# Platine_2_smd.net
KiCad netlist of a schematic drawn in EAGLE
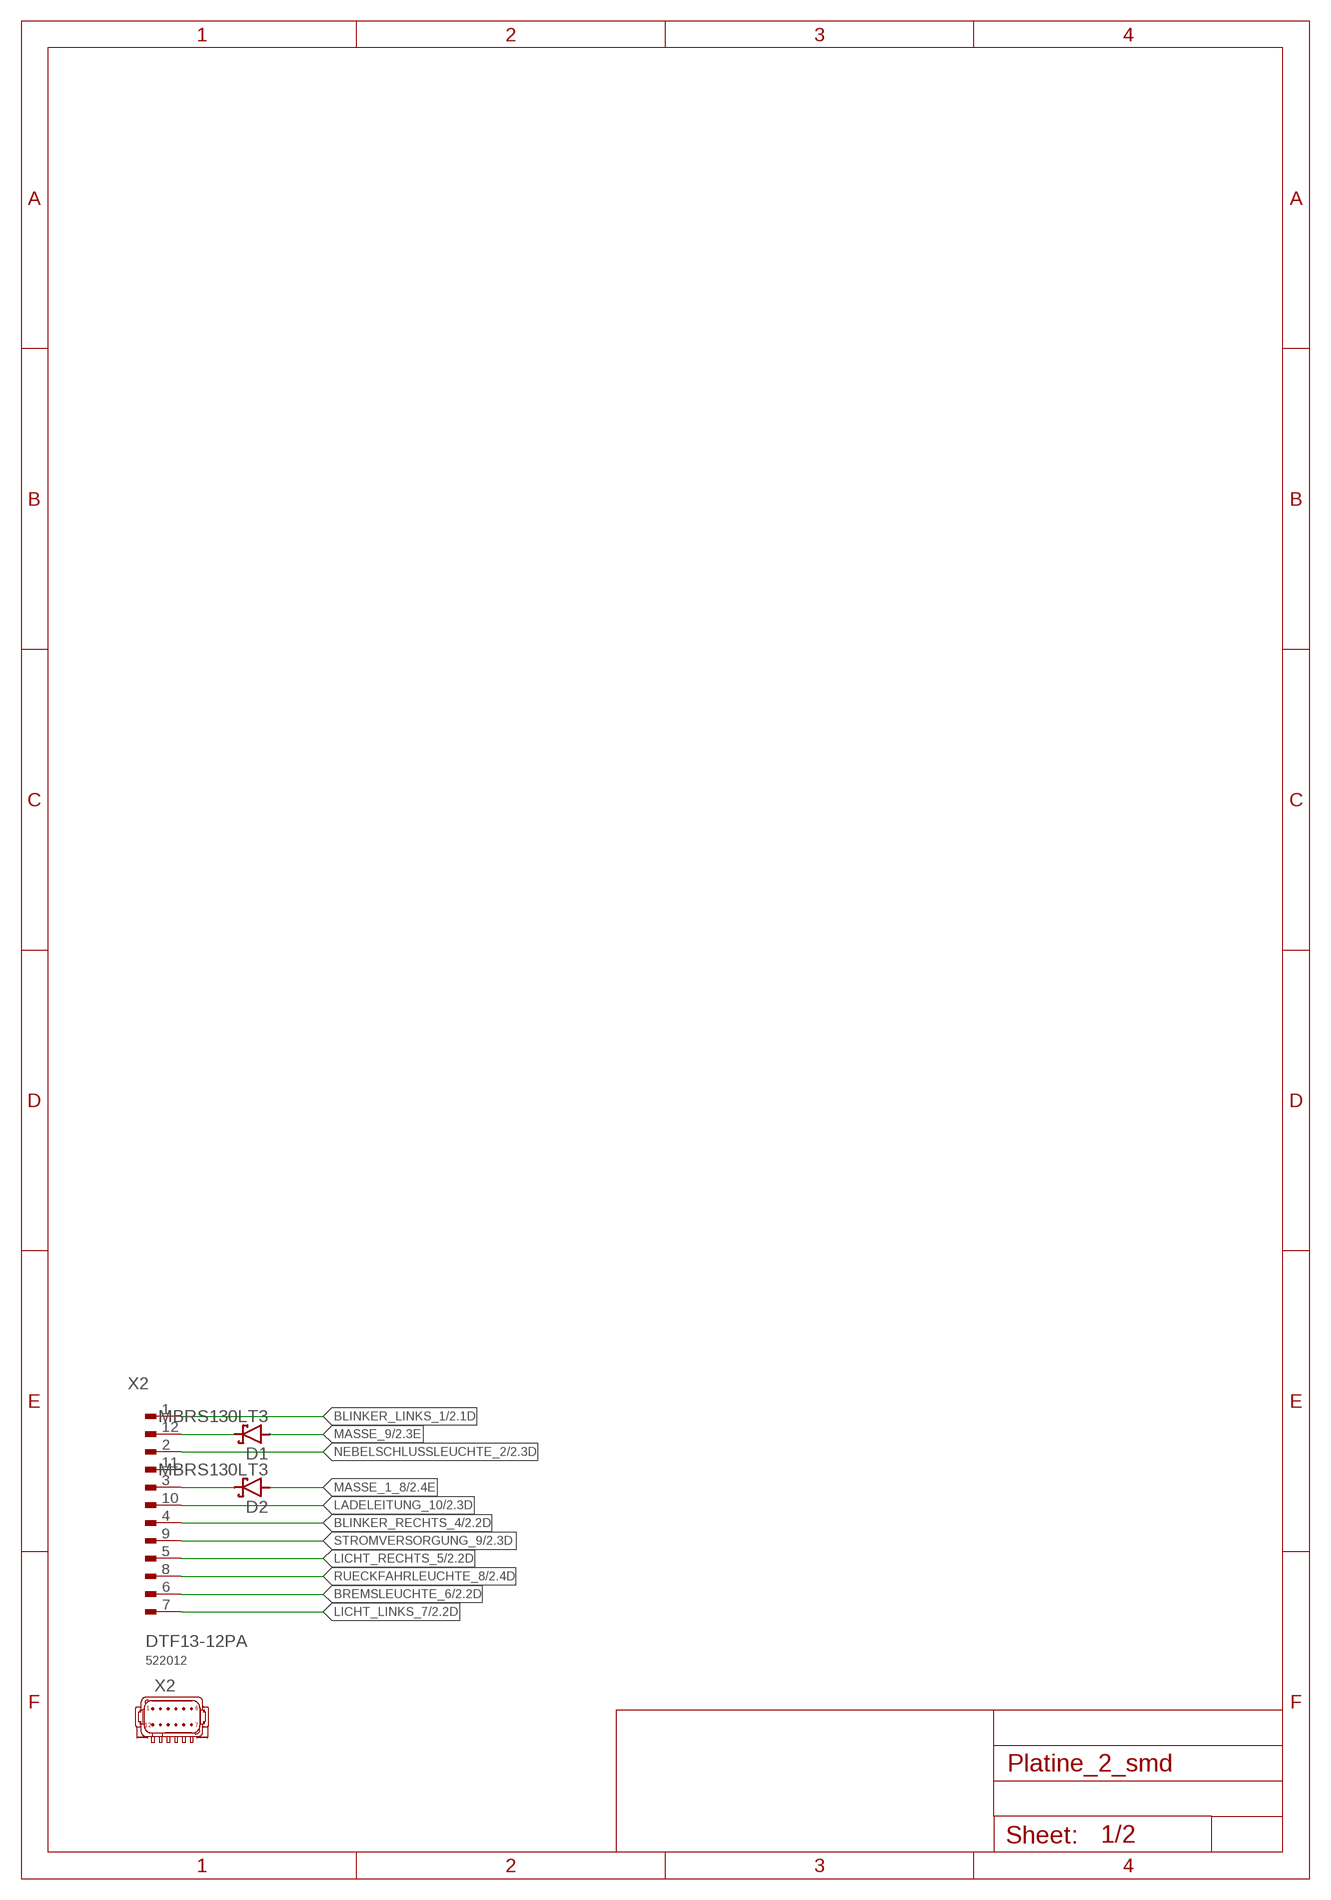
[diagram p0: schematic, sheet 1]
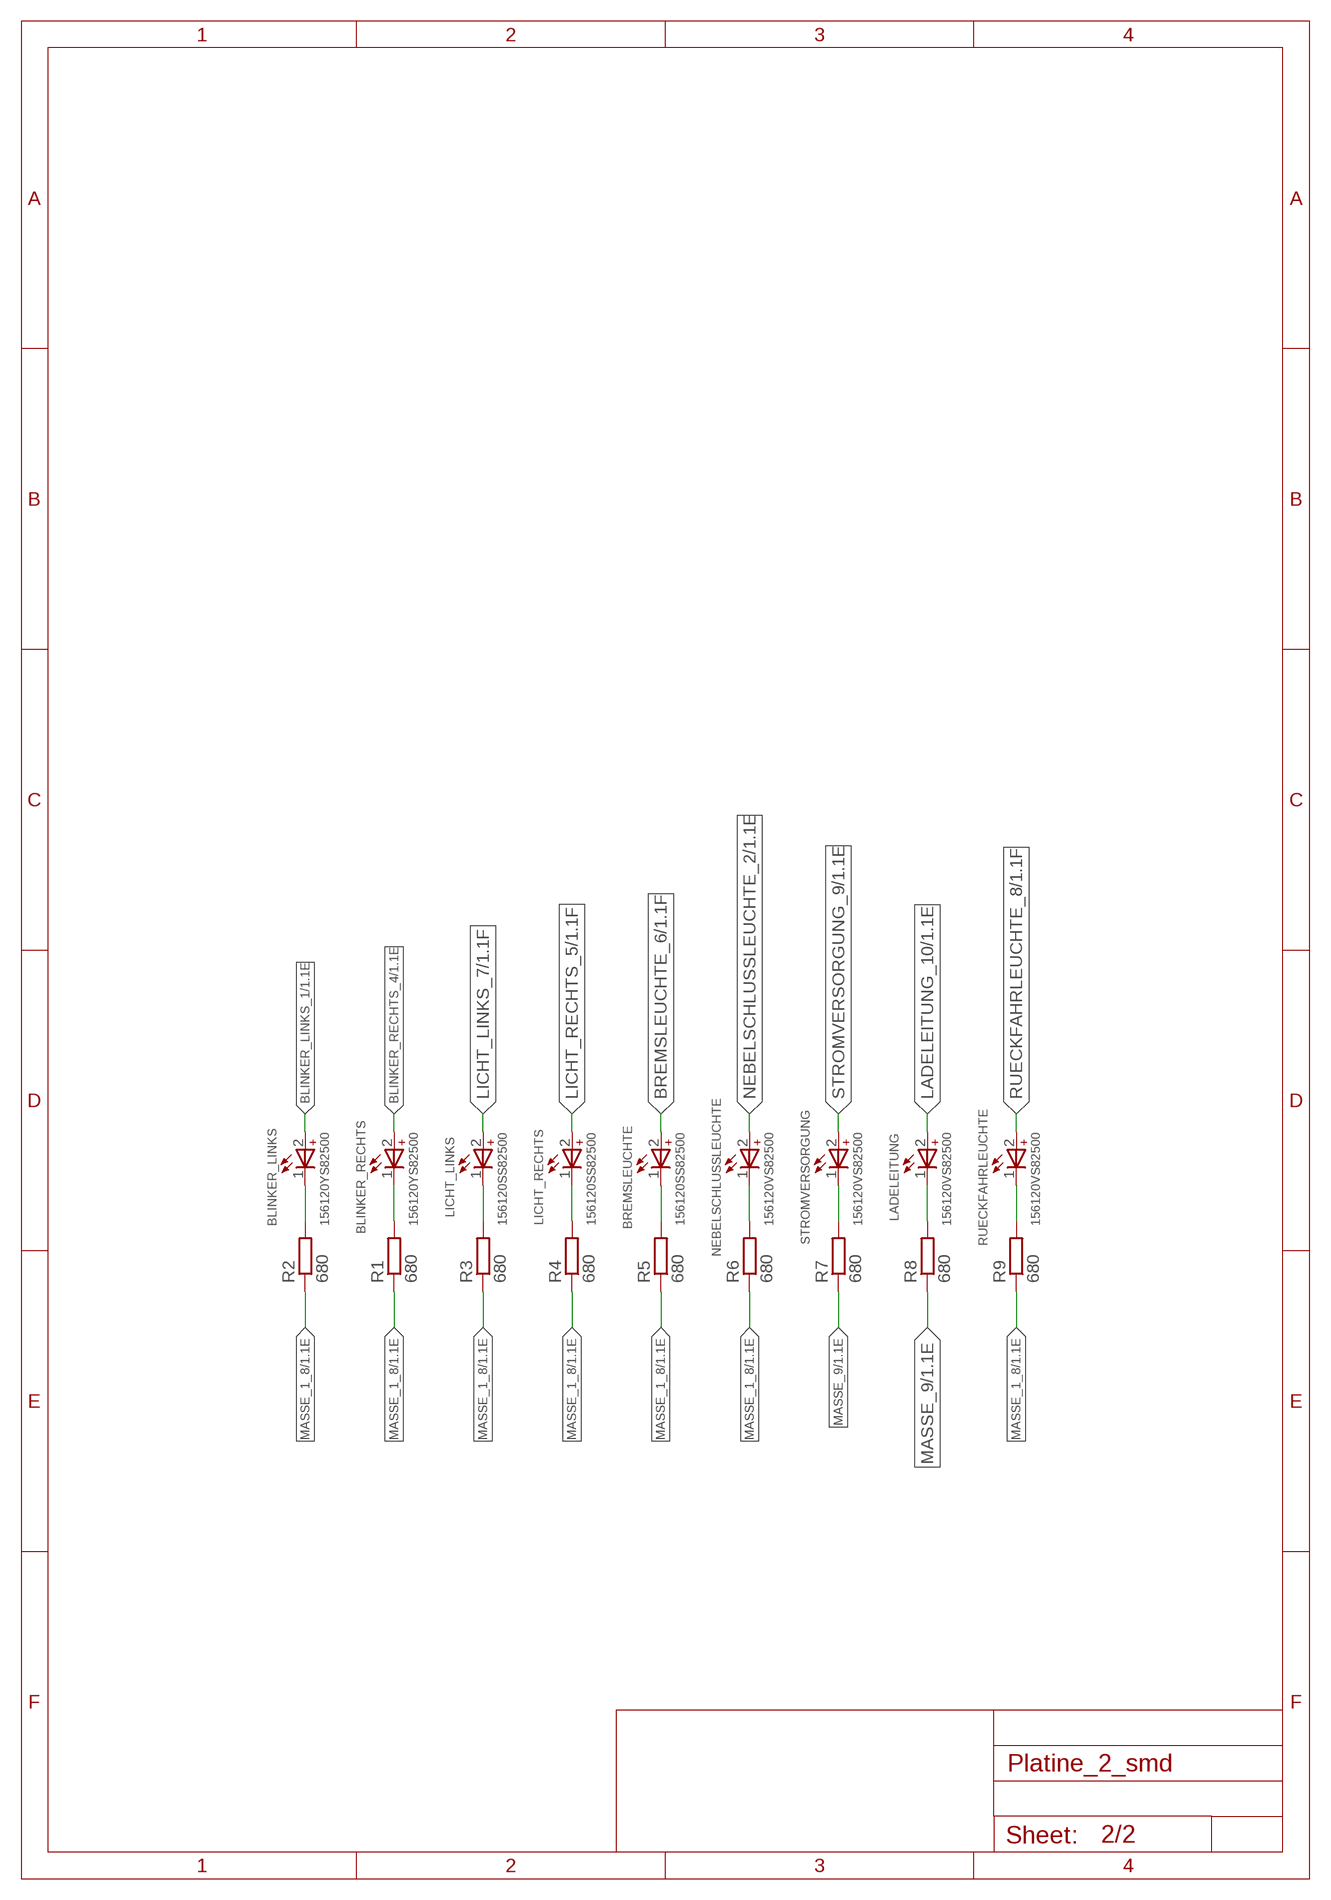
[diagram p1: schematic, sheet 2]

(export (version "E")
  (design (tool "Eeschema 10.0.6"))
  (components
    (comp (ref "BLINKER_LINKS")
      (value "156120YS82500")
      (footprint "eagle-import:WL-SMRW_1206_DOME_REV")
      (libsource (lib "eagle-import") (part "WL-SMRW_1206_DOME_REV_156120YS82500"))
    )
    (comp (ref "BLINKER_RECHTS")
      (value "156120YS82500")
      (footprint "eagle-import:WL-SMRW_1206_DOME_REV")
      (libsource (lib "eagle-import") (part "WL-SMRW_1206_DOME_REV_156120YS82500"))
    )
    (comp (ref "BREMSLEUCHTE")
      (value "156120SS82500")
      (footprint "eagle-import:WL-SMRW_1206_DOME_REV")
      (libsource (lib "eagle-import") (part "WL-SMRW_1206_DOME_REV_156120SS82500"))
    )
    (comp (ref "LADELEITUNG")
      (value "156120VS82500")
      (footprint "eagle-import:WL-SMRW_1206_DOME_REV")
      (libsource (lib "eagle-import") (part "WL-SMRW_1206_DOME_REV_156120SS82500"))
    )
    (comp (ref "LICHT_LINKS")
      (value "156120SS82500")
      (footprint "eagle-import:WL-SMRW_1206_DOME_REV")
      (libsource (lib "eagle-import") (part "WL-SMRW_1206_DOME_REV_156120SS82500"))
    )
    (comp (ref "LICHT_RECHTS")
      (value "156120SS82500")
      (footprint "eagle-import:WL-SMRW_1206_DOME_REV")
      (libsource (lib "eagle-import") (part "WL-SMRW_1206_DOME_REV_156120SS82500"))
    )
    (comp (ref "NEBELSCHLUSSLEUCHTE")
      (value "156120VS82500")
      (footprint "eagle-import:WL-SMRW_1206_DOME_REV")
      (libsource (lib "eagle-import") (part "WL-SMRW_1206_DOME_REV_156120SS82500"))
    )
    (comp (ref "R1")
      (value "680")
      (footprint "eagle-import:R1206")
      (libsource (lib "eagle-import") (part "R-EU_R1206"))
    )
    (comp (ref "R2")
      (value "680")
      (footprint "eagle-import:R1206")
      (libsource (lib "eagle-import") (part "R-EU_R1206"))
    )
    (comp (ref "R3")
      (value "680")
      (footprint "eagle-import:R1206")
      (libsource (lib "eagle-import") (part "R-EU_R1206"))
    )
    (comp (ref "R4")
      (value "680")
      (footprint "eagle-import:R1206")
      (libsource (lib "eagle-import") (part "R-EU_R1206"))
    )
    (comp (ref "R5")
      (value "680")
      (footprint "eagle-import:R1206")
      (libsource (lib "eagle-import") (part "R-EU_R1206"))
    )
    (comp (ref "R6")
      (value "680")
      (footprint "eagle-import:R1206")
      (libsource (lib "eagle-import") (part "R-EU_R1206"))
    )
    (comp (ref "R7")
      (value "680")
      (footprint "eagle-import:R1206")
      (libsource (lib "eagle-import") (part "R-EU_R1206"))
    )
    (comp (ref "R8")
      (value "680")
      (footprint "eagle-import:R1206")
      (libsource (lib "eagle-import") (part "R-EU_R1206"))
    )
    (comp (ref "R9")
      (value "680")
      (footprint "eagle-import:R1206")
      (libsource (lib "eagle-import") (part "R-EU_R1206"))
    )
    (comp (ref "RUECKFAHRLEUCHTE")
      (value "156120VS82500")
      (footprint "eagle-import:WL-SMRW_1206_DOME_REV")
      (libsource (lib "eagle-import") (part "WL-SMRW_1206_DOME_REV_156120SS82500"))
    )
    (comp (ref "STROMVERSORGUNG")
      (value "156120VS82500")
      (footprint "eagle-import:WL-SMRW_1206_DOME_REV")
      (libsource (lib "eagle-import") (part "WL-SMRW_1206_DOME_REV_156120SS82500"))
    )
    (comp (ref "D1")
      (value "MBRS130LT3")
      (footprint "eagle-import:SMB")
      (libsource (lib "eagle-import") (part "MBRS130LT3"))
    )
    (comp (ref "D2")
      (value "MBRS130LT3")
      (footprint "eagle-import:SMB")
      (libsource (lib "eagle-import") (part "MBRS130LT3"))
    )
    (comp (ref "X2")
      (value "DTF13-12PA")
      (footprint "eagle-import:DTF13-12PA")
      (fields (field (name "ARTIKEL_NR") "522012"))
      (libsource (lib "eagle-import") (part "DTF13-12PA"))
    )
  )
  (nets
    (net (code "1") (name "BLINKER_LINKS_1") (class "Default")
      (node (ref "BLINKER_LINKS") (pin "2") (pinfunction "+_2") (pintype "passive"))
      (node (ref "X2") (pin "1") (pinfunction "1_1") (pintype "passive"))
    )
    (net (code "2") (name "BLINKER_RECHTS_4") (class "Default")
      (node (ref "BLINKER_RECHTS") (pin "2") (pinfunction "+_2") (pintype "passive"))
      (node (ref "X2") (pin "4") (pinfunction "4_4") (pintype "passive"))
    )
    (net (code "3") (name "BREMSLEUCHTE_6") (class "Default")
      (node (ref "BREMSLEUCHTE") (pin "2") (pinfunction "+_2") (pintype "passive"))
      (node (ref "X2") (pin "6") (pinfunction "6_6") (pintype "passive"))
    )
    (net (code "4") (name "LADELEITUNG_10") (class "Default")
      (node (ref "LADELEITUNG") (pin "2") (pinfunction "+_2") (pintype "passive"))
      (node (ref "X2") (pin "10") (pinfunction "10_10") (pintype "passive"))
    )
    (net (code "5") (name "LICHT_LINKS_7") (class "Default")
      (node (ref "LICHT_LINKS") (pin "2") (pinfunction "+_2") (pintype "passive"))
      (node (ref "X2") (pin "7") (pinfunction "7_7") (pintype "passive"))
    )
    (net (code "6") (name "LICHT_RECHTS_5") (class "Default")
      (node (ref "LICHT_RECHTS") (pin "2") (pinfunction "+_2") (pintype "passive"))
      (node (ref "X2") (pin "5") (pinfunction "5_5") (pintype "passive"))
    )
    (net (code "7") (name "MASSE_1_8") (class "Default")
      (node (ref "D2") (pin "A") (pinfunction "A_A") (pintype "passive"))
      (node (ref "R1") (pin "1") (pinfunction "1_1") (pintype "passive"))
      (node (ref "R2") (pin "1") (pinfunction "1_1") (pintype "passive"))
      (node (ref "R3") (pin "1") (pinfunction "1_1") (pintype "passive"))
      (node (ref "R4") (pin "1") (pinfunction "1_1") (pintype "passive"))
      (node (ref "R5") (pin "1") (pinfunction "1_1") (pintype "passive"))
      (node (ref "R6") (pin "1") (pinfunction "1_1") (pintype "passive"))
      (node (ref "R9") (pin "1") (pinfunction "1_1") (pintype "passive"))
    )
    (net (code "8") (name "MASSE_9") (class "Default")
      (node (ref "D1") (pin "A") (pinfunction "A_A") (pintype "passive"))
      (node (ref "R7") (pin "1") (pinfunction "1_1") (pintype "passive"))
      (node (ref "R8") (pin "1") (pinfunction "1_1") (pintype "passive"))
    )
    (net (code "9") (name "NEBELSCHLUSSLEUCHTE_2") (class "Default")
      (node (ref "NEBELSCHLUSSLEUCHTE") (pin "2") (pinfunction "+_2") (pintype "passive"))
      (node (ref "X2") (pin "2") (pinfunction "2_2") (pintype "passive"))
    )
    (net (code "10") (name "Net-(BLINKER_LINKS--)") (class "Default")
      (node (ref "BLINKER_LINKS") (pin "1") (pinfunction "-_1") (pintype "passive"))
      (node (ref "R2") (pin "2") (pinfunction "2_2") (pintype "passive"))
    )
    (net (code "11") (name "Net-(BLINKER_RECHTS--)") (class "Default")
      (node (ref "BLINKER_RECHTS") (pin "1") (pinfunction "-_1") (pintype "passive"))
      (node (ref "R1") (pin "2") (pinfunction "2_2") (pintype "passive"))
    )
    (net (code "12") (name "Net-(BREMSLEUCHTE--)") (class "Default")
      (node (ref "BREMSLEUCHTE") (pin "1") (pinfunction "-_1") (pintype "passive"))
      (node (ref "R5") (pin "2") (pinfunction "2_2") (pintype "passive"))
    )
    (net (code "13") (name "Net-(D1-PadC)") (class "Default")
      (node (ref "D1") (pin "C") (pinfunction "C_C") (pintype "passive"))
      (node (ref "X2") (pin "12") (pinfunction "12_12") (pintype "passive"))
    )
    (net (code "14") (name "Net-(D2-PadC)") (class "Default")
      (node (ref "D2") (pin "C") (pinfunction "C_C") (pintype "passive"))
      (node (ref "X2") (pin "3") (pinfunction "3_3") (pintype "passive"))
    )
    (net (code "15") (name "Net-(LADELEITUNG--)") (class "Default")
      (node (ref "LADELEITUNG") (pin "1") (pinfunction "-_1") (pintype "passive"))
      (node (ref "R8") (pin "2") (pinfunction "2_2") (pintype "passive"))
    )
    (net (code "16") (name "Net-(LICHT_LINKS--)") (class "Default")
      (node (ref "LICHT_LINKS") (pin "1") (pinfunction "-_1") (pintype "passive"))
      (node (ref "R3") (pin "2") (pinfunction "2_2") (pintype "passive"))
    )
    (net (code "17") (name "Net-(LICHT_RECHTS--)") (class "Default")
      (node (ref "LICHT_RECHTS") (pin "1") (pinfunction "-_1") (pintype "passive"))
      (node (ref "R4") (pin "2") (pinfunction "2_2") (pintype "passive"))
    )
    (net (code "18") (name "Net-(NEBELSCHLUSSLEUCHTE--)") (class "Default")
      (node (ref "NEBELSCHLUSSLEUCHTE") (pin "1") (pinfunction "-_1") (pintype "passive"))
      (node (ref "R6") (pin "2") (pinfunction "2_2") (pintype "passive"))
    )
    (net (code "19") (name "Net-(RUECKFAHRLEUCHTE--)") (class "Default")
      (node (ref "R9") (pin "2") (pinfunction "2_2") (pintype "passive"))
      (node (ref "RUECKFAHRLEUCHTE") (pin "1") (pinfunction "-_1") (pintype "passive"))
    )
    (net (code "20") (name "Net-(STROMVERSORGUNG--)") (class "Default")
      (node (ref "R7") (pin "2") (pinfunction "2_2") (pintype "passive"))
      (node (ref "STROMVERSORGUNG") (pin "1") (pinfunction "-_1") (pintype "passive"))
    )
    (net (code "21") (name "RUECKFAHRLEUCHTE_8") (class "Default")
      (node (ref "RUECKFAHRLEUCHTE") (pin "2") (pinfunction "+_2") (pintype "passive"))
      (node (ref "X2") (pin "8") (pinfunction "8_8") (pintype "passive"))
    )
    (net (code "22") (name "STROMVERSORGUNG_9") (class "Default")
      (node (ref "STROMVERSORGUNG") (pin "2") (pinfunction "+_2") (pintype "passive"))
      (node (ref "X2") (pin "9") (pinfunction "9_9") (pintype "passive"))
    )
    (net (code "23") (name "unconnected-(X2-Pad11)") (class "Default")
      (node (ref "X2") (pin "11") (pinfunction "11_11") (pintype "passive"))
    )
  )
)
